# Yahtzee.net
KiCad netlist of a schematic drawn in EAGLE
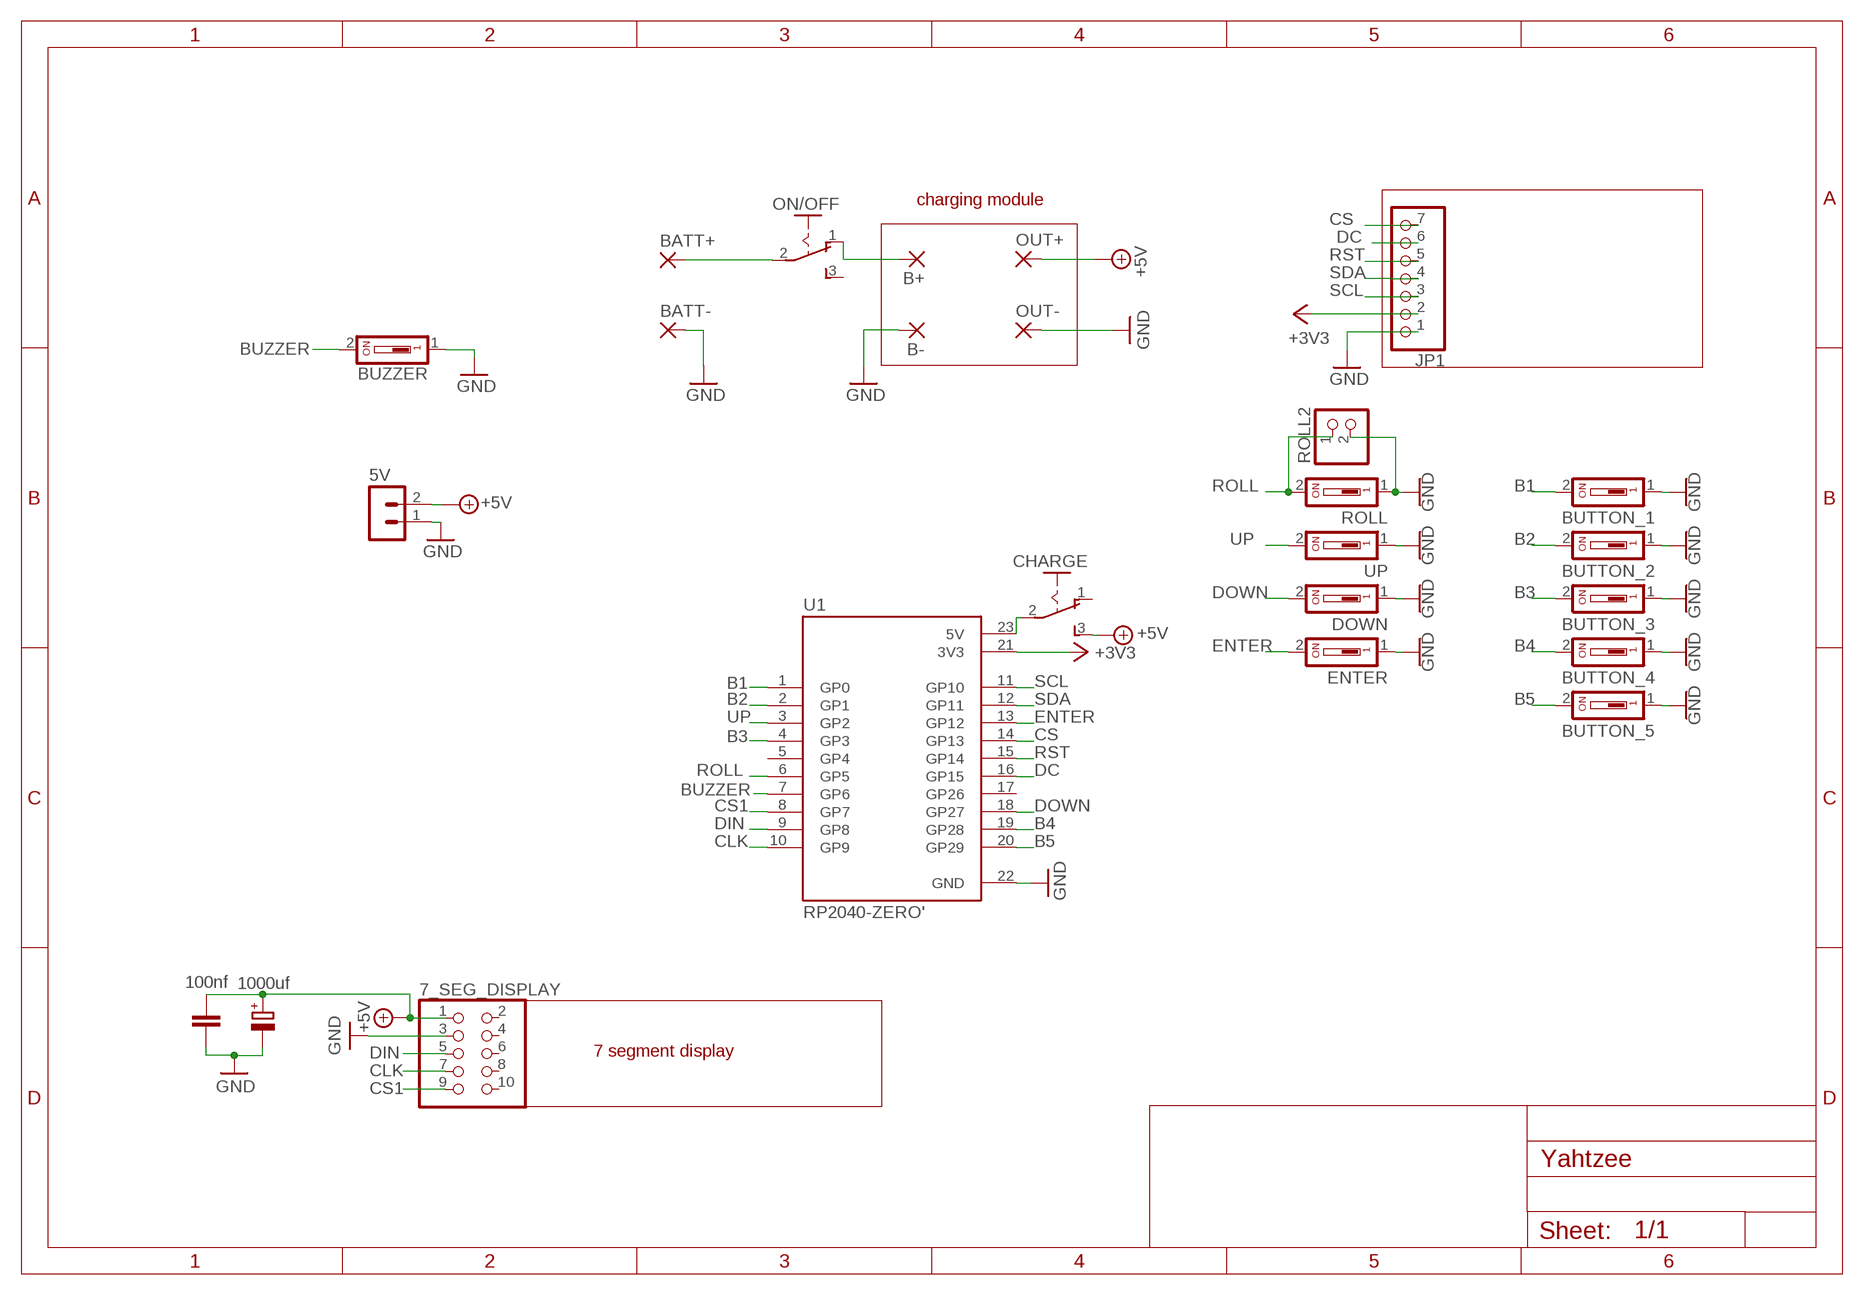
[diagram p0: schematic, sheet 1]

(export (version "E")
  (design (tool "Eeschema 10.0.6"))
  (components
    (comp (ref "5V")
      (value "B2B-PH-K-S")
      (footprint "eagle-import:B2B-PH-K-S")
      (libsource (lib "eagle-import") (part "B2B-PH-K-S"))
    )
    (comp (ref "7_SEG_DISPLAY")
      (value "PINHD-2X5")
      (footprint "eagle-import:2X05")
      (libsource (lib "eagle-import") (part "PINHD-2X5"))
    )
    (comp (ref "B+")
      (value "SMD5")
      (footprint "eagle-import:SMD2,54-5,08")
      (libsource (lib "eagle-import") (part "SMD5"))
    )
    (comp (ref "B-")
      (value "SMD5")
      (footprint "eagle-import:SMD2,54-5,08")
      (libsource (lib "eagle-import") (part "SMD5"))
    )
    (comp (ref "BATT+")
      (value "SMD5")
      (footprint "eagle-import:SMD2,54-5,08")
      (libsource (lib "eagle-import") (part "SMD5"))
    )
    (comp (ref "BATT-")
      (value "SMD5")
      (footprint "eagle-import:SMD2,54-5,08")
      (libsource (lib "eagle-import") (part "SMD5"))
    )
    (comp (ref "BUTTON_1")
      (value "DS01")
      (footprint "eagle-import:DS-01")
      (libsource (lib "eagle-import") (part "DS01"))
    )
    (comp (ref "BUTTON_2")
      (value "DS01")
      (footprint "eagle-import:DS-01")
      (libsource (lib "eagle-import") (part "DS01"))
    )
    (comp (ref "BUTTON_3")
      (value "DS01")
      (footprint "eagle-import:DS-01")
      (libsource (lib "eagle-import") (part "DS01"))
    )
    (comp (ref "BUTTON_4")
      (value "DS01")
      (footprint "eagle-import:DS-01")
      (libsource (lib "eagle-import") (part "DS01"))
    )
    (comp (ref "BUTTON_5")
      (value "DS01")
      (footprint "eagle-import:DS-01")
      (libsource (lib "eagle-import") (part "DS01"))
    )
    (comp (ref "BUZZER")
      (value "DS01")
      (footprint "eagle-import:DS-01")
      (libsource (lib "eagle-import") (part "buzzer_DS01"))
    )
    (comp (ref "C1")
      (value "100nf")
      (footprint "eagle-import:C050-024X044")
      (libsource (lib "eagle-import") (part "C-EU050-024X044"))
    )
    (comp (ref "C2")
      (value "1000uf")
      (footprint "eagle-import:E2,5-7")
      (libsource (lib "eagle-import") (part "CPOL-EUE2.5-7"))
    )
    (comp (ref "CHARGE")
      (value "M251")
      (footprint "eagle-import:M251")
      (libsource (lib "eagle-import") (part "M251"))
    )
    (comp (ref "DOWN")
      (value "DS01")
      (footprint "eagle-import:DS-01")
      (libsource (lib "eagle-import") (part "DS01"))
    )
    (comp (ref "ENTER")
      (value "DS01")
      (footprint "eagle-import:DS-01")
      (libsource (lib "eagle-import") (part "DS01"))
    )
    (comp (ref "JP1")
      (value "PINHD-1X7")
      (footprint "eagle-import:1X07")
      (libsource (lib "eagle-import") (part "PINHD-1X7"))
    )
    (comp (ref "ON/OFF")
      (value "M251")
      (footprint "eagle-import:M251")
      (libsource (lib "eagle-import") (part "M251"))
    )
    (comp (ref "OUT+")
      (value "SMD5")
      (footprint "eagle-import:SMD2,54-5,08")
      (libsource (lib "eagle-import") (part "SMD5"))
    )
    (comp (ref "OUT-")
      (value "SMD5")
      (footprint "eagle-import:SMD2,54-5,08")
      (libsource (lib "eagle-import") (part "SMD5"))
    )
    (comp (ref "ROLL")
      (value "DS01")
      (footprint "eagle-import:DS-01")
      (libsource (lib "eagle-import") (part "DS01"))
    )
    (comp (ref "ROLL2")
      (value "PINHD-1X2")
      (footprint "eagle-import:1X02")
      (libsource (lib "eagle-import") (part "PINHD-1X2"))
    )
    (comp (ref "U1")
      (value "RP2040-ZERO'")
      (footprint "eagle-import:MODULE_RP2040-ZERO")
      (fields (field (name "MF") "Waveshare Electronics") (field (name "MP") "RP2040-ZERO"))
      (libsource (lib "eagle-import") (part "RP2040-ZERO'"))
    )
    (comp (ref "UP")
      (value "DS01")
      (footprint "eagle-import:DS-01")
      (libsource (lib "eagle-import") (part "DS01"))
    )
  )
  (nets
    (net (code "1") (name "+3V3") (class "Default")
      (node (ref "JP1") (pin "2") (pinfunction "2_2") (pintype "passive"))
      (node (ref "U1") (pin "21") (pinfunction "3V3_21") (pintype "power_in"))
    )
    (net (code "2") (name "+5V") (class "Default")
      (node (ref "5V") (pin "2") (pinfunction "2_2") (pintype "passive"))
      (node (ref "7_SEG_DISPLAY") (pin "1") (pinfunction "1_1") (pintype "passive"))
      (node (ref "C1") (pin "1") (pinfunction "1_1") (pintype "passive"))
      (node (ref "C2") (pin "+") (pinfunction "+_+") (pintype "passive"))
      (node (ref "CHARGE") (pin "3") (pinfunction "S_3") (pintype "passive"))
      (node (ref "OUT+") (pin "1") (pinfunction "P_1") (pintype "passive"))
    )
    (net (code "3") (name "/B1") (class "Default")
      (node (ref "BUTTON_1") (pin "2") (pinfunction "2_2") (pintype "passive"))
      (node (ref "U1") (pin "1") (pinfunction "GP0_1") (pintype "bidirectional"))
    )
    (net (code "4") (name "/B2") (class "Default")
      (node (ref "BUTTON_2") (pin "2") (pinfunction "2_2") (pintype "passive"))
      (node (ref "U1") (pin "2") (pinfunction "GP1_2") (pintype "bidirectional"))
    )
    (net (code "5") (name "/B3") (class "Default")
      (node (ref "BUTTON_3") (pin "2") (pinfunction "2_2") (pintype "passive"))
      (node (ref "U1") (pin "4") (pinfunction "GP3_4") (pintype "bidirectional"))
    )
    (net (code "6") (name "/B4") (class "Default")
      (node (ref "BUTTON_4") (pin "2") (pinfunction "2_2") (pintype "passive"))
      (node (ref "U1") (pin "19") (pinfunction "GP28_19") (pintype "bidirectional"))
    )
    (net (code "7") (name "/B5") (class "Default")
      (node (ref "BUTTON_5") (pin "2") (pinfunction "2_2") (pintype "passive"))
      (node (ref "U1") (pin "20") (pinfunction "GP29_20") (pintype "bidirectional"))
    )
    (net (code "8") (name "/BUZZER") (class "Default")
      (node (ref "BUZZER") (pin "2") (pinfunction "2_2") (pintype "passive"))
      (node (ref "U1") (pin "7") (pinfunction "GP6_7") (pintype "bidirectional"))
    )
    (net (code "9") (name "/CLK") (class "Default")
      (node (ref "7_SEG_DISPLAY") (pin "7") (pinfunction "7_7") (pintype "passive"))
      (node (ref "U1") (pin "10") (pinfunction "GP9_10") (pintype "bidirectional"))
    )
    (net (code "10") (name "/CS") (class "Default")
      (node (ref "JP1") (pin "7") (pinfunction "7_7") (pintype "passive"))
      (node (ref "U1") (pin "14") (pinfunction "GP13_14") (pintype "bidirectional"))
    )
    (net (code "11") (name "/CS1") (class "Default")
      (node (ref "7_SEG_DISPLAY") (pin "9") (pinfunction "9_9") (pintype "passive"))
      (node (ref "U1") (pin "8") (pinfunction "GP7_8") (pintype "bidirectional"))
    )
    (net (code "12") (name "/DC") (class "Default")
      (node (ref "JP1") (pin "6") (pinfunction "6_6") (pintype "passive"))
      (node (ref "U1") (pin "16") (pinfunction "GP15_16") (pintype "bidirectional"))
    )
    (net (code "13") (name "/DIN") (class "Default")
      (node (ref "7_SEG_DISPLAY") (pin "5") (pinfunction "5_5") (pintype "passive"))
      (node (ref "U1") (pin "9") (pinfunction "GP8_9") (pintype "bidirectional"))
    )
    (net (code "14") (name "/DOWN") (class "Default")
      (node (ref "DOWN") (pin "2") (pinfunction "2_2") (pintype "passive"))
      (node (ref "U1") (pin "18") (pinfunction "GP27_18") (pintype "bidirectional"))
    )
    (net (code "15") (name "/ENTER") (class "Default")
      (node (ref "ENTER") (pin "2") (pinfunction "2_2") (pintype "passive"))
      (node (ref "U1") (pin "13") (pinfunction "GP12_13") (pintype "bidirectional"))
    )
    (net (code "16") (name "/ROLL") (class "Default")
      (node (ref "ROLL") (pin "2") (pinfunction "2_2") (pintype "passive"))
      (node (ref "ROLL2") (pin "1") (pinfunction "1_1") (pintype "passive"))
      (node (ref "U1") (pin "6") (pinfunction "GP5_6") (pintype "bidirectional"))
    )
    (net (code "17") (name "/RST") (class "Default")
      (node (ref "JP1") (pin "5") (pinfunction "5_5") (pintype "passive"))
      (node (ref "U1") (pin "15") (pinfunction "GP14_15") (pintype "bidirectional"))
    )
    (net (code "18") (name "/SCL") (class "Default")
      (node (ref "JP1") (pin "3") (pinfunction "3_3") (pintype "passive"))
      (node (ref "U1") (pin "11") (pinfunction "GP10_11") (pintype "bidirectional"))
    )
    (net (code "19") (name "/SDA") (class "Default")
      (node (ref "JP1") (pin "4") (pinfunction "4_4") (pintype "passive"))
      (node (ref "U1") (pin "12") (pinfunction "GP11_12") (pintype "bidirectional"))
    )
    (net (code "20") (name "/UP") (class "Default")
      (node (ref "U1") (pin "3") (pinfunction "GP2_3") (pintype "bidirectional"))
      (node (ref "UP") (pin "2") (pinfunction "2_2") (pintype "passive"))
    )
    (net (code "21") (name "GND") (class "Default")
      (node (ref "5V") (pin "1") (pinfunction "1_1") (pintype "passive"))
      (node (ref "7_SEG_DISPLAY") (pin "3") (pinfunction "3_3") (pintype "passive"))
      (node (ref "B-") (pin "1") (pinfunction "P_1") (pintype "passive"))
      (node (ref "BATT-") (pin "1") (pinfunction "P_1") (pintype "passive"))
      (node (ref "BUTTON_1") (pin "1") (pinfunction "1_1") (pintype "passive"))
      (node (ref "BUTTON_2") (pin "1") (pinfunction "1_1") (pintype "passive"))
      (node (ref "BUTTON_3") (pin "1") (pinfunction "1_1") (pintype "passive"))
      (node (ref "BUTTON_4") (pin "1") (pinfunction "1_1") (pintype "passive"))
      (node (ref "BUTTON_5") (pin "1") (pinfunction "1_1") (pintype "passive"))
      (node (ref "BUZZER") (pin "1") (pinfunction "1_1") (pintype "passive"))
      (node (ref "C1") (pin "2") (pinfunction "2_2") (pintype "passive"))
      (node (ref "C2") (pin "-") (pinfunction "-_-") (pintype "passive"))
      (node (ref "DOWN") (pin "1") (pinfunction "1_1") (pintype "passive"))
      (node (ref "ENTER") (pin "1") (pinfunction "1_1") (pintype "passive"))
      (node (ref "JP1") (pin "1") (pinfunction "1_1") (pintype "passive"))
      (node (ref "OUT-") (pin "1") (pinfunction "P_1") (pintype "passive"))
      (node (ref "ROLL") (pin "1") (pinfunction "1_1") (pintype "passive"))
      (node (ref "ROLL2") (pin "2") (pinfunction "2_2") (pintype "passive"))
      (node (ref "U1") (pin "22") (pinfunction "GND_22") (pintype "power_in"))
      (node (ref "UP") (pin "1") (pinfunction "1_1") (pintype "passive"))
    )
    (net (code "22") (name "Net-(B+-P)") (class "Default")
      (node (ref "B+") (pin "1") (pinfunction "P_1") (pintype "passive"))
      (node (ref "ON/OFF") (pin "1") (pinfunction "O_1") (pintype "passive"))
    )
    (net (code "23") (name "Net-(BATT+-P)") (class "Default")
      (node (ref "BATT+") (pin "1") (pinfunction "P_1") (pintype "passive"))
      (node (ref "ON/OFF") (pin "2") (pinfunction "P_2") (pintype "passive"))
    )
    (net (code "24") (name "Net-(CHARGE-P)") (class "Default")
      (node (ref "CHARGE") (pin "2") (pinfunction "P_2") (pintype "passive"))
      (node (ref "U1") (pin "23") (pinfunction "5V_23") (pintype "power_in"))
    )
    (net (code "25") (name "unconnected-(7_SEG_DISPLAY-Pad2)") (class "Default")
      (node (ref "7_SEG_DISPLAY") (pin "2") (pinfunction "2_2") (pintype "passive"))
    )
    (net (code "26") (name "unconnected-(7_SEG_DISPLAY-Pad4)") (class "Default")
      (node (ref "7_SEG_DISPLAY") (pin "4") (pinfunction "4_4") (pintype "passive"))
    )
    (net (code "27") (name "unconnected-(7_SEG_DISPLAY-Pad6)") (class "Default")
      (node (ref "7_SEG_DISPLAY") (pin "6") (pinfunction "6_6") (pintype "passive"))
    )
    (net (code "28") (name "unconnected-(7_SEG_DISPLAY-Pad8)") (class "Default")
      (node (ref "7_SEG_DISPLAY") (pin "8") (pinfunction "8_8") (pintype "passive"))
    )
    (net (code "29") (name "unconnected-(7_SEG_DISPLAY-Pad10)") (class "Default")
      (node (ref "7_SEG_DISPLAY") (pin "10") (pinfunction "10_10") (pintype "passive"))
    )
    (net (code "30") (name "unconnected-(CHARGE-O-Pad1)") (class "Default")
      (node (ref "CHARGE") (pin "1") (pinfunction "O_1") (pintype "passive"))
    )
    (net (code "31") (name "unconnected-(ON/OFF-S-Pad3)") (class "Default")
      (node (ref "ON/OFF") (pin "3") (pinfunction "S_3") (pintype "passive"))
    )
    (net (code "32") (name "unconnected-(U1-GP4-Pad5)") (class "Default")
      (node (ref "U1") (pin "5") (pinfunction "GP4_5") (pintype "bidirectional"))
    )
    (net (code "33") (name "unconnected-(U1-GP26-Pad17)") (class "Default")
      (node (ref "U1") (pin "17") (pinfunction "GP26_17") (pintype "bidirectional"))
    )
  )
)
